# opa313.net
KiCad netlist of a schematic drawn in Altium Designer
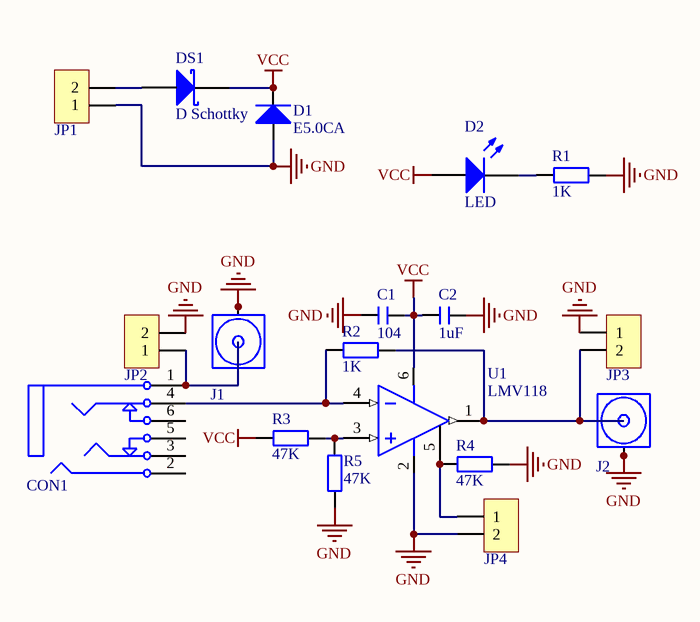
[diagram p0: opa313.SchDoc]

(export (version "E")
  (design (tool "Eeschema 10.0.6"))
  (components
    (comp (ref "C1")
      (value "104")
      (footprint "C 0603")
      (description "无极性贴片电容")
      (fields (field (name "版权归属") "源创客"))
      (libsource (lib "电阻-电容-电感") (part "C"))
    )
    (comp (ref "C2")
      (value "1uF")
      (footprint "C 0603")
      (description "无极性贴片电容")
      (fields (field (name "版权归属") "源创客"))
      (libsource (lib "电阻-电容-电感") (part "C"))
    )
    (comp (ref "CON1")
      (value "PJ342")
      (footprint "PJ342A")
      (description "3.5耳机插座,4Pin")
      (fields (field (name "版权归属") "源创客"))
      (libsource (lib "接口类") (part "PJ342"))
    )
    (comp (ref "D1")
      (value "TVS")
      (footprint "DIODE-SMA")
      (description "TVS保护")
      (fields (field (name "TYPE") "E5.0CA") (field (name "PUBLISHER") "Altium Limited"))
      (libsource (lib "LIB") (part "TVS"))
    )
    (comp (ref "D2")
      (value "LED")
      (footprint "0603")
      (description "发光二极管")
      (fields (field (name "PUBLISHER") "Altium Limited"))
      (libsource (lib "LIB") (part "LED"))
    )
    (comp (ref "DS1")
      (value "D Schottky")
      (footprint "DIODE-SMA")
      (description "Schottky Diode")
      (fields (field (name "PUBLISHER") "Altium Limited"))
      (libsource (lib "LIB") (part "D Schottky"))
    )
    (comp (ref "J1") (value "COAX") (footprint "MCX5.08-5-H") (libsource (lib "LIB") (part "COAX")))
    (comp (ref "J2") (value "COAX") (footprint "MCX5.08-5-H") (libsource (lib "LIB") (part "COAX")))
    (comp (ref "JP1")
      (value "HDR-1X2")
      (footprint "XH2.54-2P_H")
      (description "2P接插件")
      (fields (field (name "版权归属") "源创客"))
      (libsource (lib "接插件") (part "Header 2"))
    )
    (comp (ref "JP2")
      (value "HDR-1X2")
      (footprint "HDR-1X2")
      (description "2P接插件")
      (fields (field (name "版权归属") "源创客"))
      (libsource (lib "接插件") (part "Header 2"))
    )
    (comp (ref "JP3")
      (value "HDR-1X2")
      (footprint "HDR-1X2")
      (description "2P接插件")
      (fields (field (name "版权归属") "源创客"))
      (libsource (lib "") (part "Header 2_1"))
    )
    (comp (ref "JP4")
      (value "HDR-1X2")
      (footprint "HDR-1X2")
      (description "2P接插件")
      (fields (field (name "版权归属") "源创客"))
      (libsource (lib "") (part "Header 2_1"))
    )
    (comp (ref "R1")
      (value "1K")
      (footprint "R 0603")
      (description "贴片电阻")
      (fields (field (name "版权归属") "源创客"))
      (libsource (lib "电阻-电容-电感") (part "R"))
    )
    (comp (ref "R2")
      (value "1K")
      (footprint "R 0805")
      (description "贴片电阻")
      (fields (field (name "版权归属") "源创客"))
      (libsource (lib "电阻-电容-电感") (part "R"))
    )
    (comp (ref "R3")
      (value "47K")
      (footprint "R 0603")
      (description "贴片电阻")
      (fields (field (name "版权归属") "源创客"))
      (libsource (lib "电阻-电容-电感") (part "R"))
    )
    (comp (ref "R4")
      (value "47K")
      (footprint "R 0603")
      (description "贴片电阻")
      (fields (field (name "版权归属") "源创客"))
      (libsource (lib "电阻-电容-电感") (part "R"))
    )
    (comp (ref "R5")
      (value "47K")
      (footprint "R 0603")
      (description "贴片电阻")
      (fields (field (name "版权归属") "源创客"))
      (libsource (lib "电阻-电容-电感") (part "R"))
    )
    (comp (ref "U1")
      (value "LMV118")
      (footprint "SOT23-6_N")
      (description "具有关断功能的LMV11x 低电压45MHz 轨至轨输出运算放大器")
      (libsource (lib "LIB") (part "LMV118"))
    )
  )
  (nets
    (net (code "1") (name "GND") (class "Default")
      (node (ref "C1") (pin "1") (pinfunction "1_1") (pintype "passive"))
      (node (ref "C2") (pin "2") (pinfunction "2_2") (pintype "passive"))
      (node (ref "D1") (pin "1") (pinfunction "A_1") (pintype "passive"))
      (node (ref "J1") (pin "2") (pinfunction "GND_2") (pintype "passive"))
      (node (ref "J1") (pin "3") (pinfunction "GND_3") (pintype "passive"))
      (node (ref "J1") (pin "4") (pinfunction "GND_4") (pintype "passive"))
      (node (ref "J1") (pin "5") (pinfunction "GND_5") (pintype "passive"))
      (node (ref "J2") (pin "2") (pinfunction "GND_2") (pintype "passive"))
      (node (ref "J2") (pin "3") (pinfunction "GND_3") (pintype "passive"))
      (node (ref "J2") (pin "4") (pinfunction "GND_4") (pintype "passive"))
      (node (ref "J2") (pin "5") (pinfunction "GND_5") (pintype "passive"))
      (node (ref "JP1") (pin "1") (pinfunction "1_1") (pintype "passive"))
      (node (ref "JP2") (pin "2") (pinfunction "2_2") (pintype "passive"))
      (node (ref "JP3") (pin "1") (pinfunction "1_1") (pintype "passive"))
      (node (ref "JP4") (pin "2") (pinfunction "2_2") (pintype "passive"))
      (node (ref "R1") (pin "2") (pinfunction "2_2") (pintype "passive"))
      (node (ref "R4") (pin "2") (pinfunction "2_2") (pintype "passive"))
      (node (ref "R5") (pin "1") (pinfunction "1_1") (pintype "passive"))
      (node (ref "U1") (pin "2") (pinfunction "V-_2") (pintype "power_in"))
    )
    (net (code "2") (name "Net-(D2-K)") (class "Default")
      (node (ref "D2") (pin "2") (pinfunction "K_2") (pintype "passive"))
      (node (ref "R1") (pin "1") (pinfunction "1_1") (pintype "passive"))
    )
    (net (code "3") (name "Net-(DS1-Pad1)") (class "Default")
      (node (ref "DS1") (pin "1") (pinfunction "1_1") (pintype "passive"))
      (node (ref "JP1") (pin "2") (pinfunction "2_2") (pintype "passive"))
    )
    (net (code "4") (name "Net-(J1-Signal)") (class "Default")
      (node (ref "CON1") (pin "1") (pinfunction "1_1") (pintype "passive"))
      (node (ref "J1") (pin "1") (pinfunction "Signal_1") (pintype "passive"))
      (node (ref "JP2") (pin "1") (pinfunction "1_1") (pintype "passive"))
    )
    (net (code "5") (name "Net-(J2-Signal)") (class "Default")
      (node (ref "J2") (pin "1") (pinfunction "Signal_1") (pintype "passive"))
      (node (ref "JP3") (pin "2") (pinfunction "2_2") (pintype "passive"))
      (node (ref "R2") (pin "2") (pinfunction "2_2") (pintype "passive"))
      (node (ref "U1") (pin "1") (pinfunction "OUT_1") (pintype "output"))
    )
    (net (code "6") (name "Net-(U1-IN+)") (class "Default")
      (node (ref "R3") (pin "2") (pinfunction "2_2") (pintype "passive"))
      (node (ref "R5") (pin "2") (pinfunction "2_2") (pintype "passive"))
      (node (ref "U1") (pin "3") (pinfunction "IN+_3") (pintype "input"))
    )
    (net (code "7") (name "Net-(U1-IN-)") (class "Default")
      (node (ref "CON1") (pin "4") (pinfunction "4_4") (pintype "passive"))
      (node (ref "R2") (pin "1") (pinfunction "1_1") (pintype "passive"))
      (node (ref "U1") (pin "4") (pinfunction "IN-_4") (pintype "input"))
    )
    (net (code "8") (name "Net-(U1-SD)") (class "Default")
      (node (ref "JP4") (pin "1") (pinfunction "1_1") (pintype "passive"))
      (node (ref "R4") (pin "1") (pinfunction "1_1") (pintype "passive"))
      (node (ref "U1") (pin "5") (pinfunction "SD_5") (pintype "passive"))
    )
    (net (code "9") (name "VCC") (class "Default")
      (node (ref "C1") (pin "2") (pinfunction "2_2") (pintype "passive"))
      (node (ref "C2") (pin "1") (pinfunction "1_1") (pintype "passive"))
      (node (ref "D1") (pin "2") (pinfunction "K_2") (pintype "passive"))
      (node (ref "D2") (pin "1") (pinfunction "A_1") (pintype "passive"))
      (node (ref "DS1") (pin "2") (pinfunction "2_2") (pintype "passive"))
      (node (ref "R3") (pin "1") (pinfunction "1_1") (pintype "passive"))
      (node (ref "U1") (pin "6") (pinfunction "V+_6") (pintype "power_in"))
    )
    (net (code "10") (name "unconnected-(CON1-Pad2)") (class "Default")
      (node (ref "CON1") (pin "2") (pinfunction "2_2") (pintype "passive"))
    )
    (net (code "11") (name "unconnected-(CON1-Pad3)") (class "Default")
      (node (ref "CON1") (pin "3") (pinfunction "3_3") (pintype "passive"))
    )
    (net (code "12") (name "unconnected-(CON1-Pad5)") (class "Default")
      (node (ref "CON1") (pin "5") (pinfunction "5_5") (pintype "passive"))
    )
    (net (code "13") (name "unconnected-(CON1-Pad6)") (class "Default")
      (node (ref "CON1") (pin "6") (pinfunction "6_6") (pintype "passive"))
    )
  )
)
